# wifi.net
KiCad netlist of a schematic drawn in EAGLE
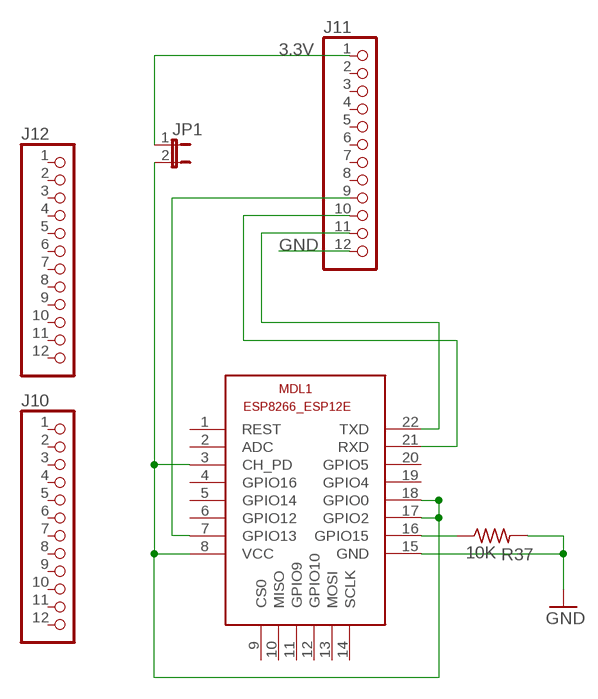
[diagram p0: schematic, sheet 1]

(export (version "E")
  (design (tool "Eeschema 10.0.6"))
  (components
    (comp (ref "J10")
      (value "PINHD-1X12")
      (footprint "eagle-import:1X12")
      (libsource (lib "eagle-import") (part "PINHD-1X12"))
    )
    (comp (ref "J11")
      (value "PINHD-1X12")
      (footprint "eagle-import:1X12")
      (libsource (lib "eagle-import") (part "PINHD-1X12"))
    )
    (comp (ref "J12")
      (value "PINHD-1X12")
      (footprint "eagle-import:1X12")
      (libsource (lib "eagle-import") (part "PINHD-1X12"))
    )
    (comp (ref "JP1")
      (value "JP1E")
      (footprint "eagle-import:JP1")
      (libsource (lib "eagle-import") (part "JP1E"))
    )
    (comp (ref "MDL1")
      (value "ESP8266-12EESP8266-ESP12E")
      (footprint "eagle-import:ESP8266-ESP12E")
      (libsource (lib "eagle-import") (part "ESP8266-12EESP8266-ESP12E"))
    )
    (comp (ref "R37")
      (value "10K")
      (footprint "eagle-import:R0805")
      (libsource (lib "eagle-import") (part "R-US_R0805"))
    )
  )
  (nets
    (net (code "1") (name "/3.3V") (class "Default")
      (node (ref "J11") (pin "1") (pinfunction "1_1") (pintype "passive"))
      (node (ref "JP1") (pin "1") (pinfunction "1_1") (pintype "passive"))
    )
    (net (code "2") (name "GND") (class "Default")
      (node (ref "J11") (pin "12") (pinfunction "12_12") (pintype "passive"))
      (node (ref "MDL1") (pin "15") (pinfunction "GND_15") (pintype "bidirectional"))
      (node (ref "R37") (pin "2") (pinfunction "2_2") (pintype "passive"))
    )
    (net (code "3") (name "Net-(MDL1-CH_PD)") (class "Default")
      (node (ref "JP1") (pin "2") (pinfunction "2_2") (pintype "passive"))
      (node (ref "MDL1") (pin "17") (pinfunction "GPIO2_17") (pintype "bidirectional"))
      (node (ref "MDL1") (pin "18") (pinfunction "GPIO0_18") (pintype "bidirectional"))
      (node (ref "MDL1") (pin "3") (pinfunction "CH_PD_3") (pintype "bidirectional"))
      (node (ref "MDL1") (pin "8") (pinfunction "VCC_8") (pintype "bidirectional"))
    )
    (net (code "4") (name "Net-(MDL1-GPIO13)") (class "Default")
      (node (ref "J11") (pin "9") (pinfunction "9_9") (pintype "passive"))
      (node (ref "MDL1") (pin "7") (pinfunction "GPIO13_7") (pintype "bidirectional"))
    )
    (net (code "5") (name "Net-(MDL1-GPIO15)") (class "Default")
      (node (ref "MDL1") (pin "16") (pinfunction "GPIO15_16") (pintype "bidirectional"))
      (node (ref "R37") (pin "1") (pinfunction "1_1") (pintype "passive"))
    )
    (net (code "6") (name "Net-(MDL1-RXD)") (class "Default")
      (node (ref "J11") (pin "10") (pinfunction "10_10") (pintype "passive"))
      (node (ref "MDL1") (pin "21") (pinfunction "RXD_21") (pintype "bidirectional"))
    )
    (net (code "7") (name "Net-(MDL1-TXD)") (class "Default")
      (node (ref "J11") (pin "11") (pinfunction "11_11") (pintype "passive"))
      (node (ref "MDL1") (pin "22") (pinfunction "TXD_22") (pintype "bidirectional"))
    )
    (net (code "8") (name "unconnected-(J10-Pad1)") (class "Default")
      (node (ref "J10") (pin "1") (pinfunction "1_1") (pintype "passive"))
    )
    (net (code "9") (name "unconnected-(J10-Pad2)") (class "Default")
      (node (ref "J10") (pin "2") (pinfunction "2_2") (pintype "passive"))
    )
    (net (code "10") (name "unconnected-(J10-Pad3)") (class "Default")
      (node (ref "J10") (pin "3") (pinfunction "3_3") (pintype "passive"))
    )
    (net (code "11") (name "unconnected-(J10-Pad4)") (class "Default")
      (node (ref "J10") (pin "4") (pinfunction "4_4") (pintype "passive"))
    )
    (net (code "12") (name "unconnected-(J10-Pad5)") (class "Default")
      (node (ref "J10") (pin "5") (pinfunction "5_5") (pintype "passive"))
    )
    (net (code "13") (name "unconnected-(J10-Pad6)") (class "Default")
      (node (ref "J10") (pin "6") (pinfunction "6_6") (pintype "passive"))
    )
    (net (code "14") (name "unconnected-(J10-Pad7)") (class "Default")
      (node (ref "J10") (pin "7") (pinfunction "7_7") (pintype "passive"))
    )
    (net (code "15") (name "unconnected-(J10-Pad8)") (class "Default")
      (node (ref "J10") (pin "8") (pinfunction "8_8") (pintype "passive"))
    )
    (net (code "16") (name "unconnected-(J10-Pad9)") (class "Default")
      (node (ref "J10") (pin "9") (pinfunction "9_9") (pintype "passive"))
    )
    (net (code "17") (name "unconnected-(J10-Pad10)") (class "Default")
      (node (ref "J10") (pin "10") (pinfunction "10_10") (pintype "passive"))
    )
    (net (code "18") (name "unconnected-(J10-Pad11)") (class "Default")
      (node (ref "J10") (pin "11") (pinfunction "11_11") (pintype "passive"))
    )
    (net (code "19") (name "unconnected-(J10-Pad12)") (class "Default")
      (node (ref "J10") (pin "12") (pinfunction "12_12") (pintype "passive"))
    )
    (net (code "20") (name "unconnected-(J11-Pad2)") (class "Default")
      (node (ref "J11") (pin "2") (pinfunction "2_2") (pintype "passive"))
    )
    (net (code "21") (name "unconnected-(J11-Pad3)") (class "Default")
      (node (ref "J11") (pin "3") (pinfunction "3_3") (pintype "passive"))
    )
    (net (code "22") (name "unconnected-(J11-Pad4)") (class "Default")
      (node (ref "J11") (pin "4") (pinfunction "4_4") (pintype "passive"))
    )
    (net (code "23") (name "unconnected-(J11-Pad5)") (class "Default")
      (node (ref "J11") (pin "5") (pinfunction "5_5") (pintype "passive"))
    )
    (net (code "24") (name "unconnected-(J11-Pad6)") (class "Default")
      (node (ref "J11") (pin "6") (pinfunction "6_6") (pintype "passive"))
    )
    (net (code "25") (name "unconnected-(J11-Pad7)") (class "Default")
      (node (ref "J11") (pin "7") (pinfunction "7_7") (pintype "passive"))
    )
    (net (code "26") (name "unconnected-(J11-Pad8)") (class "Default")
      (node (ref "J11") (pin "8") (pinfunction "8_8") (pintype "passive"))
    )
    (net (code "27") (name "unconnected-(J12-Pad1)") (class "Default")
      (node (ref "J12") (pin "1") (pinfunction "1_1") (pintype "passive"))
    )
    (net (code "28") (name "unconnected-(J12-Pad2)") (class "Default")
      (node (ref "J12") (pin "2") (pinfunction "2_2") (pintype "passive"))
    )
    (net (code "29") (name "unconnected-(J12-Pad3)") (class "Default")
      (node (ref "J12") (pin "3") (pinfunction "3_3") (pintype "passive"))
    )
    (net (code "30") (name "unconnected-(J12-Pad4)") (class "Default")
      (node (ref "J12") (pin "4") (pinfunction "4_4") (pintype "passive"))
    )
    (net (code "31") (name "unconnected-(J12-Pad5)") (class "Default")
      (node (ref "J12") (pin "5") (pinfunction "5_5") (pintype "passive"))
    )
    (net (code "32") (name "unconnected-(J12-Pad6)") (class "Default")
      (node (ref "J12") (pin "6") (pinfunction "6_6") (pintype "passive"))
    )
    (net (code "33") (name "unconnected-(J12-Pad7)") (class "Default")
      (node (ref "J12") (pin "7") (pinfunction "7_7") (pintype "passive"))
    )
    (net (code "34") (name "unconnected-(J12-Pad8)") (class "Default")
      (node (ref "J12") (pin "8") (pinfunction "8_8") (pintype "passive"))
    )
    (net (code "35") (name "unconnected-(J12-Pad9)") (class "Default")
      (node (ref "J12") (pin "9") (pinfunction "9_9") (pintype "passive"))
    )
    (net (code "36") (name "unconnected-(J12-Pad10)") (class "Default")
      (node (ref "J12") (pin "10") (pinfunction "10_10") (pintype "passive"))
    )
    (net (code "37") (name "unconnected-(J12-Pad11)") (class "Default")
      (node (ref "J12") (pin "11") (pinfunction "11_11") (pintype "passive"))
    )
    (net (code "38") (name "unconnected-(J12-Pad12)") (class "Default")
      (node (ref "J12") (pin "12") (pinfunction "12_12") (pintype "passive"))
    )
    (net (code "39") (name "unconnected-(MDL1-ADC-Pad2)") (class "Default")
      (node (ref "MDL1") (pin "2") (pinfunction "ADC_2") (pintype "bidirectional"))
    )
    (net (code "40") (name "unconnected-(MDL1-CS0-Pad9)") (class "Default")
      (node (ref "MDL1") (pin "9") (pinfunction "CS0_9") (pintype "bidirectional"))
    )
    (net (code "41") (name "unconnected-(MDL1-GPIO4-Pad19)") (class "Default")
      (node (ref "MDL1") (pin "19") (pinfunction "GPIO4_19") (pintype "bidirectional"))
    )
    (net (code "42") (name "unconnected-(MDL1-GPIO5-Pad20)") (class "Default")
      (node (ref "MDL1") (pin "20") (pinfunction "GPIO5_20") (pintype "bidirectional"))
    )
    (net (code "43") (name "unconnected-(MDL1-GPIO9-Pad11)") (class "Default")
      (node (ref "MDL1") (pin "11") (pinfunction "GPIO9_11") (pintype "bidirectional"))
    )
    (net (code "44") (name "unconnected-(MDL1-GPIO10-Pad12)") (class "Default")
      (node (ref "MDL1") (pin "12") (pinfunction "GPIO10_12") (pintype "bidirectional"))
    )
    (net (code "45") (name "unconnected-(MDL1-GPIO12-Pad6)") (class "Default")
      (node (ref "MDL1") (pin "6") (pinfunction "GPIO12_6") (pintype "bidirectional"))
    )
    (net (code "46") (name "unconnected-(MDL1-GPIO14-Pad5)") (class "Default")
      (node (ref "MDL1") (pin "5") (pinfunction "GPIO14_5") (pintype "bidirectional"))
    )
    (net (code "47") (name "unconnected-(MDL1-GPIO16-Pad4)") (class "Default")
      (node (ref "MDL1") (pin "4") (pinfunction "GPIO16_4") (pintype "bidirectional"))
    )
    (net (code "48") (name "unconnected-(MDL1-MISO-Pad10)") (class "Default")
      (node (ref "MDL1") (pin "10") (pinfunction "MISO_10") (pintype "bidirectional"))
    )
    (net (code "49") (name "unconnected-(MDL1-MOSI-Pad13)") (class "Default")
      (node (ref "MDL1") (pin "13") (pinfunction "MOSI_13") (pintype "bidirectional"))
    )
    (net (code "50") (name "unconnected-(MDL1-REST-Pad1)") (class "Default")
      (node (ref "MDL1") (pin "1") (pinfunction "REST_1") (pintype "bidirectional"))
    )
    (net (code "51") (name "unconnected-(MDL1-SCLK-Pad14)") (class "Default")
      (node (ref "MDL1") (pin "14") (pinfunction "SCLK_14") (pintype "bidirectional"))
    )
  )
)
